# Cube_Schematic.net
KiCad netlist of a schematic drawn in EAGLE
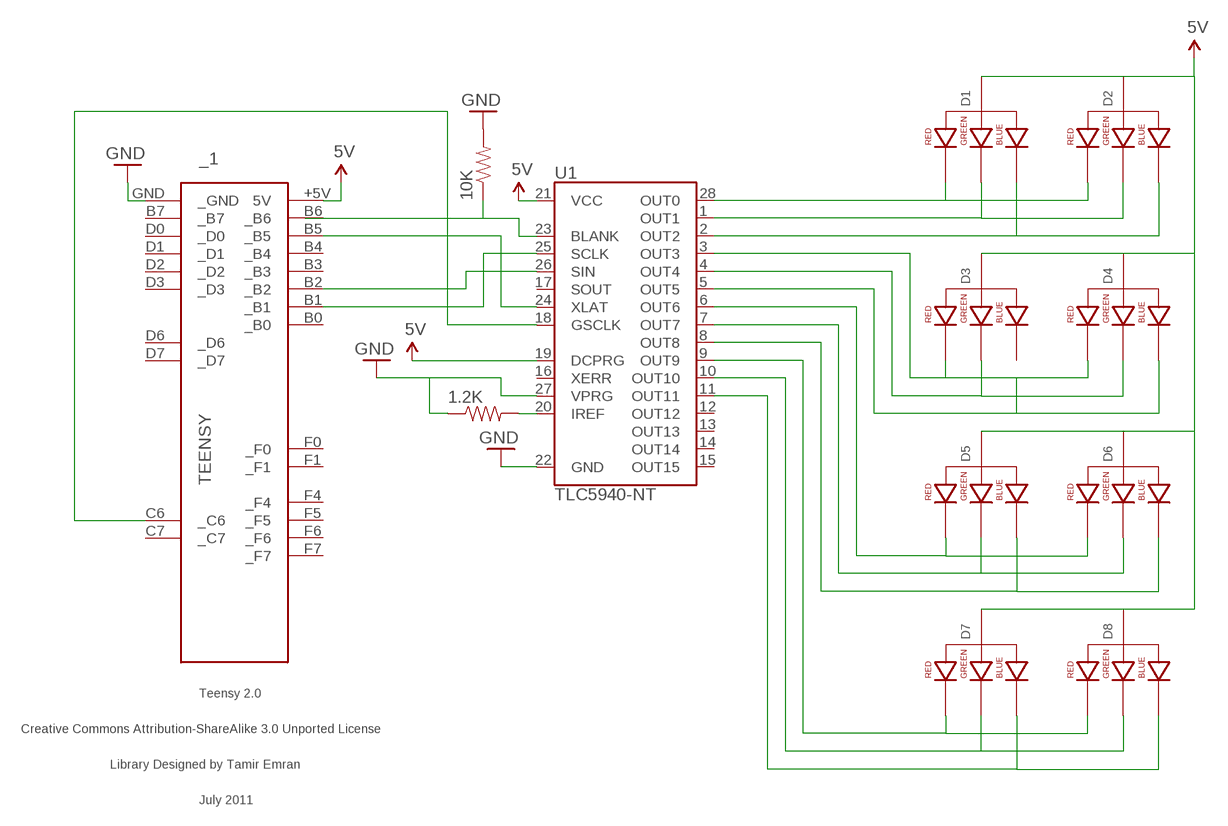
[diagram p0: schematic, sheet 1]

(export (version "E")
  (design (tool "Eeschema 10.0.6"))
  (components
    (comp (ref "1.2K")
      (value "RESISTOREZ")
      (footprint "eagle-import:AXIAL-0.3EZ")
      (libsource (lib "eagle-import") (part "RESISTOREZ"))
    )
    (comp (ref "10K")
      (value "RESISTOREZ")
      (footprint "eagle-import:AXIAL-0.3EZ")
      (libsource (lib "eagle-import") (part "RESISTOREZ"))
    )
    (comp (ref "D1")
      (value "LED-RGB-CA-THRUDIFFUSE")
      (footprint "eagle-import:LED-RGB-THRU")
      (libsource (lib "eagle-import") (part "LED-RGB-CA-THRUDIFFUSE"))
    )
    (comp (ref "D2")
      (value "LED-RGB-CA-THRUDIFFUSE")
      (footprint "eagle-import:LED-RGB-THRU")
      (libsource (lib "eagle-import") (part "LED-RGB-CA-THRUDIFFUSE"))
    )
    (comp (ref "D3")
      (value "LED-RGB-CA-THRUDIFFUSE")
      (footprint "eagle-import:LED-RGB-THRU")
      (libsource (lib "eagle-import") (part "LED-RGB-CA-THRUDIFFUSE"))
    )
    (comp (ref "D4")
      (value "LED-RGB-CA-THRUDIFFUSE")
      (footprint "eagle-import:LED-RGB-THRU")
      (libsource (lib "eagle-import") (part "LED-RGB-CA-THRUDIFFUSE"))
    )
    (comp (ref "D5")
      (value "LED-RGB-CA-THRUDIFFUSE")
      (footprint "eagle-import:LED-RGB-THRU")
      (libsource (lib "eagle-import") (part "LED-RGB-CA-THRUDIFFUSE"))
    )
    (comp (ref "D6")
      (value "LED-RGB-CA-THRUDIFFUSE")
      (footprint "eagle-import:LED-RGB-THRU")
      (libsource (lib "eagle-import") (part "LED-RGB-CA-THRUDIFFUSE"))
    )
    (comp (ref "D7")
      (value "LED-RGB-CA-THRUDIFFUSE")
      (footprint "eagle-import:LED-RGB-THRU")
      (libsource (lib "eagle-import") (part "LED-RGB-CA-THRUDIFFUSE"))
    )
    (comp (ref "D8")
      (value "LED-RGB-CA-THRUDIFFUSE")
      (footprint "eagle-import:LED-RGB-THRU")
      (libsource (lib "eagle-import") (part "LED-RGB-CA-THRUDIFFUSE"))
    )
    (comp (ref "U1")
      (value "TLC5940-NT")
      (footprint "eagle-import:DIL28-3")
      (libsource (lib "eagle-import") (part "TLC5940-NT"))
    )
    (comp (ref "_1")
      (value "TEENSY")
      (footprint "eagle-import:TEENSY")
      (libsource (lib "eagle-import") (part "TEENSY"))
    )
  )
  (nets
    (net (code "1") (name "5V") (class "Default")
      (node (ref "D1") (pin "2") (pinfunction "ANODE_2") (pintype "bidirectional"))
      (node (ref "D2") (pin "2") (pinfunction "ANODE_2") (pintype "bidirectional"))
      (node (ref "D3") (pin "2") (pinfunction "ANODE_2") (pintype "bidirectional"))
      (node (ref "D4") (pin "2") (pinfunction "ANODE_2") (pintype "bidirectional"))
      (node (ref "D5") (pin "2") (pinfunction "ANODE_2") (pintype "bidirectional"))
      (node (ref "D6") (pin "2") (pinfunction "ANODE_2") (pintype "bidirectional"))
      (node (ref "D7") (pin "2") (pinfunction "ANODE_2") (pintype "bidirectional"))
      (node (ref "D8") (pin "2") (pinfunction "ANODE_2") (pintype "bidirectional"))
      (node (ref "U1") (pin "19") (pinfunction "DCPRG_19") (pintype "bidirectional"))
      (node (ref "U1") (pin "21") (pinfunction "VCC_21") (pintype "bidirectional"))
      (node (ref "_1") (pin "+5V") (pinfunction "5V_+5V") (pintype "bidirectional"))
    )
    (net (code "2") (name "GND") (class "Default")
      (node (ref "1.2K") (pin "P$1") (pinfunction "1_P$1") (pintype "passive"))
      (node (ref "10K") (pin "P$2") (pinfunction "2_P$2") (pintype "passive"))
      (node (ref "U1") (pin "22") (pinfunction "GND_22") (pintype "bidirectional"))
      (node (ref "U1") (pin "27") (pinfunction "VPRG_27") (pintype "bidirectional"))
      (node (ref "_1") (pin "GND") (pinfunction "_GND_GND") (pintype "bidirectional"))
    )
    (net (code "3") (name "Net-(1.2K-2)") (class "Default")
      (node (ref "1.2K") (pin "P$2") (pinfunction "2_P$2") (pintype "passive"))
      (node (ref "U1") (pin "20") (pinfunction "IREF_20") (pintype "bidirectional"))
    )
    (net (code "4") (name "Net-(10K-1)") (class "Default")
      (node (ref "10K") (pin "P$1") (pinfunction "1_P$1") (pintype "passive"))
      (node (ref "U1") (pin "23") (pinfunction "BLANK_23") (pintype "bidirectional"))
    )
    (net (code "5") (name "Net-(D1-BLUE_CATHODE)") (class "Default")
      (node (ref "D1") (pin "4") (pinfunction "BLUE_CATHODE_4") (pintype "bidirectional"))
      (node (ref "D2") (pin "4") (pinfunction "BLUE_CATHODE_4") (pintype "bidirectional"))
      (node (ref "U1") (pin "2") (pinfunction "OUT2_2") (pintype "bidirectional"))
    )
    (net (code "6") (name "Net-(D1-GREEN_CATHODE)") (class "Default")
      (node (ref "D1") (pin "3") (pinfunction "GREEN_CATHODE_3") (pintype "bidirectional"))
      (node (ref "D2") (pin "3") (pinfunction "GREEN_CATHODE_3") (pintype "bidirectional"))
      (node (ref "U1") (pin "1") (pinfunction "OUT1_1") (pintype "bidirectional"))
    )
    (net (code "7") (name "Net-(D1-RED_CATHODE)") (class "Default")
      (node (ref "D1") (pin "1") (pinfunction "RED_CATHODE_1") (pintype "bidirectional"))
      (node (ref "D2") (pin "1") (pinfunction "RED_CATHODE_1") (pintype "bidirectional"))
      (node (ref "U1") (pin "28") (pinfunction "OUT0_28") (pintype "bidirectional"))
    )
    (net (code "8") (name "Net-(D3-GREEN_CATHODE)") (class "Default")
      (node (ref "D3") (pin "3") (pinfunction "GREEN_CATHODE_3") (pintype "bidirectional"))
      (node (ref "D4") (pin "3") (pinfunction "GREEN_CATHODE_3") (pintype "bidirectional"))
      (node (ref "U1") (pin "4") (pinfunction "OUT4_4") (pintype "bidirectional"))
    )
    (net (code "9") (name "Net-(D3-RED_CATHODE)") (class "Default")
      (node (ref "D3") (pin "1") (pinfunction "RED_CATHODE_1") (pintype "bidirectional"))
      (node (ref "D4") (pin "1") (pinfunction "RED_CATHODE_1") (pintype "bidirectional"))
      (node (ref "D4") (pin "4") (pinfunction "BLUE_CATHODE_4") (pintype "bidirectional"))
      (node (ref "U1") (pin "3") (pinfunction "OUT3_3") (pintype "bidirectional"))
      (node (ref "U1") (pin "5") (pinfunction "OUT5_5") (pintype "bidirectional"))
    )
    (net (code "10") (name "Net-(D5-BLUE_CATHODE)") (class "Default")
      (node (ref "D5") (pin "4") (pinfunction "BLUE_CATHODE_4") (pintype "bidirectional"))
      (node (ref "D6") (pin "4") (pinfunction "BLUE_CATHODE_4") (pintype "bidirectional"))
      (node (ref "U1") (pin "8") (pinfunction "OUT8_8") (pintype "bidirectional"))
    )
    (net (code "11") (name "Net-(D5-GREEN_CATHODE)") (class "Default")
      (node (ref "D5") (pin "3") (pinfunction "GREEN_CATHODE_3") (pintype "bidirectional"))
      (node (ref "D6") (pin "3") (pinfunction "GREEN_CATHODE_3") (pintype "bidirectional"))
      (node (ref "U1") (pin "7") (pinfunction "OUT7_7") (pintype "bidirectional"))
    )
    (net (code "12") (name "Net-(D5-RED_CATHODE)") (class "Default")
      (node (ref "D5") (pin "1") (pinfunction "RED_CATHODE_1") (pintype "bidirectional"))
      (node (ref "D6") (pin "1") (pinfunction "RED_CATHODE_1") (pintype "bidirectional"))
      (node (ref "U1") (pin "6") (pinfunction "OUT6_6") (pintype "bidirectional"))
    )
    (net (code "13") (name "Net-(D7-BLUE_CATHODE)") (class "Default")
      (node (ref "D7") (pin "4") (pinfunction "BLUE_CATHODE_4") (pintype "bidirectional"))
      (node (ref "D8") (pin "4") (pinfunction "BLUE_CATHODE_4") (pintype "bidirectional"))
      (node (ref "U1") (pin "11") (pinfunction "OUT11_11") (pintype "bidirectional"))
    )
    (net (code "14") (name "Net-(D7-GREEN_CATHODE)") (class "Default")
      (node (ref "D7") (pin "3") (pinfunction "GREEN_CATHODE_3") (pintype "bidirectional"))
      (node (ref "D8") (pin "3") (pinfunction "GREEN_CATHODE_3") (pintype "bidirectional"))
      (node (ref "U1") (pin "10") (pinfunction "OUT10_10") (pintype "bidirectional"))
    )
    (net (code "15") (name "Net-(D7-RED_CATHODE)") (class "Default")
      (node (ref "D7") (pin "1") (pinfunction "RED_CATHODE_1") (pintype "bidirectional"))
      (node (ref "D8") (pin "1") (pinfunction "RED_CATHODE_1") (pintype "bidirectional"))
      (node (ref "U1") (pin "9") (pinfunction "OUT9_9") (pintype "bidirectional"))
    )
    (net (code "16") (name "Net-(U1-GSCLK)") (class "Default")
      (node (ref "U1") (pin "18") (pinfunction "GSCLK_18") (pintype "bidirectional"))
      (node (ref "_1") (pin "C6") (pinfunction "_C6_C6") (pintype "bidirectional"))
    )
    (net (code "17") (name "Net-(U1-SCLK)") (class "Default")
      (node (ref "U1") (pin "25") (pinfunction "SCLK_25") (pintype "bidirectional"))
      (node (ref "_1") (pin "B1") (pinfunction "_B1_B1") (pintype "bidirectional"))
    )
    (net (code "18") (name "Net-(U1-SIN)") (class "Default")
      (node (ref "U1") (pin "26") (pinfunction "SIN_26") (pintype "bidirectional"))
      (node (ref "_1") (pin "B2") (pinfunction "_B2_B2") (pintype "bidirectional"))
    )
    (net (code "19") (name "Net-(U1-XLAT)") (class "Default")
      (node (ref "U1") (pin "24") (pinfunction "XLAT_24") (pintype "bidirectional"))
      (node (ref "_1") (pin "B5") (pinfunction "_B5_B5") (pintype "bidirectional"))
    )
    (net (code "20") (name "unconnected-(D3-BLUE_CATHODE-Pad4)") (class "Default")
      (node (ref "D3") (pin "4") (pinfunction "BLUE_CATHODE_4") (pintype "bidirectional"))
    )
    (net (code "21") (name "unconnected-(U1-OUT12-Pad12)") (class "Default")
      (node (ref "U1") (pin "12") (pinfunction "OUT12_12") (pintype "bidirectional"))
    )
    (net (code "22") (name "unconnected-(U1-OUT13-Pad13)") (class "Default")
      (node (ref "U1") (pin "13") (pinfunction "OUT13_13") (pintype "bidirectional"))
    )
    (net (code "23") (name "unconnected-(U1-OUT14-Pad14)") (class "Default")
      (node (ref "U1") (pin "14") (pinfunction "OUT14_14") (pintype "bidirectional"))
    )
    (net (code "24") (name "unconnected-(U1-OUT15-Pad15)") (class "Default")
      (node (ref "U1") (pin "15") (pinfunction "OUT15_15") (pintype "bidirectional"))
    )
    (net (code "25") (name "unconnected-(U1-SOUT-Pad17)") (class "Default")
      (node (ref "U1") (pin "17") (pinfunction "SOUT_17") (pintype "bidirectional"))
    )
    (net (code "26") (name "unconnected-(U1-XERR-Pad16)") (class "Default")
      (node (ref "U1") (pin "16") (pinfunction "XERR_16") (pintype "bidirectional"))
    )
    (net (code "27") (name "unconnected-(_1-_B0-PadB0)") (class "Default")
      (node (ref "_1") (pin "B0") (pinfunction "_B0_B0") (pintype "bidirectional"))
    )
    (net (code "28") (name "unconnected-(_1-_B3-PadB3)") (class "Default")
      (node (ref "_1") (pin "B3") (pinfunction "_B3_B3") (pintype "bidirectional"))
    )
    (net (code "29") (name "unconnected-(_1-_B4-PadB4)") (class "Default")
      (node (ref "_1") (pin "B4") (pinfunction "_B4_B4") (pintype "bidirectional"))
    )
    (net (code "30") (name "unconnected-(_1-_B6-PadB6)") (class "Default")
      (node (ref "_1") (pin "B6") (pinfunction "_B6_B6") (pintype "bidirectional"))
    )
    (net (code "31") (name "unconnected-(_1-_B7-PadB7)") (class "Default")
      (node (ref "_1") (pin "B7") (pinfunction "_B7_B7") (pintype "bidirectional"))
    )
    (net (code "32") (name "unconnected-(_1-_C7-PadC7)") (class "Default")
      (node (ref "_1") (pin "C7") (pinfunction "_C7_C7") (pintype "bidirectional"))
    )
    (net (code "33") (name "unconnected-(_1-_D0-PadD0)") (class "Default")
      (node (ref "_1") (pin "D0") (pinfunction "_D0_D0") (pintype "bidirectional"))
    )
    (net (code "34") (name "unconnected-(_1-_D1-PadD1)") (class "Default")
      (node (ref "_1") (pin "D1") (pinfunction "_D1_D1") (pintype "bidirectional"))
    )
    (net (code "35") (name "unconnected-(_1-_D2-PadD2)") (class "Default")
      (node (ref "_1") (pin "D2") (pinfunction "_D2_D2") (pintype "bidirectional"))
    )
    (net (code "36") (name "unconnected-(_1-_D3-PadD3)") (class "Default")
      (node (ref "_1") (pin "D3") (pinfunction "_D3_D3") (pintype "bidirectional"))
    )
    (net (code "37") (name "unconnected-(_1-_D6-PadD6)") (class "Default")
      (node (ref "_1") (pin "D6") (pinfunction "_D6_D6") (pintype "bidirectional"))
    )
    (net (code "38") (name "unconnected-(_1-_D7-PadD7)") (class "Default")
      (node (ref "_1") (pin "D7") (pinfunction "_D7_D7") (pintype "bidirectional"))
    )
    (net (code "39") (name "unconnected-(_1-_F0-PadF0)") (class "Default")
      (node (ref "_1") (pin "F0") (pinfunction "_F0_F0") (pintype "bidirectional"))
    )
    (net (code "40") (name "unconnected-(_1-_F1-PadF1)") (class "Default")
      (node (ref "_1") (pin "F1") (pinfunction "_F1_F1") (pintype "bidirectional"))
    )
    (net (code "41") (name "unconnected-(_1-_F4-PadF4)") (class "Default")
      (node (ref "_1") (pin "F4") (pinfunction "_F4_F4") (pintype "bidirectional"))
    )
    (net (code "42") (name "unconnected-(_1-_F5-PadF5)") (class "Default")
      (node (ref "_1") (pin "F5") (pinfunction "_F5_F5") (pintype "bidirectional"))
    )
    (net (code "43") (name "unconnected-(_1-_F6-PadF6)") (class "Default")
      (node (ref "_1") (pin "F6") (pinfunction "_F6_F6") (pintype "bidirectional"))
    )
    (net (code "44") (name "unconnected-(_1-_F7-PadF7)") (class "Default")
      (node (ref "_1") (pin "F7") (pinfunction "_F7_F7") (pintype "bidirectional"))
    )
  )
)
